# 12V_BOOST.net
KiCad netlist of a schematic drawn in Altium Designer
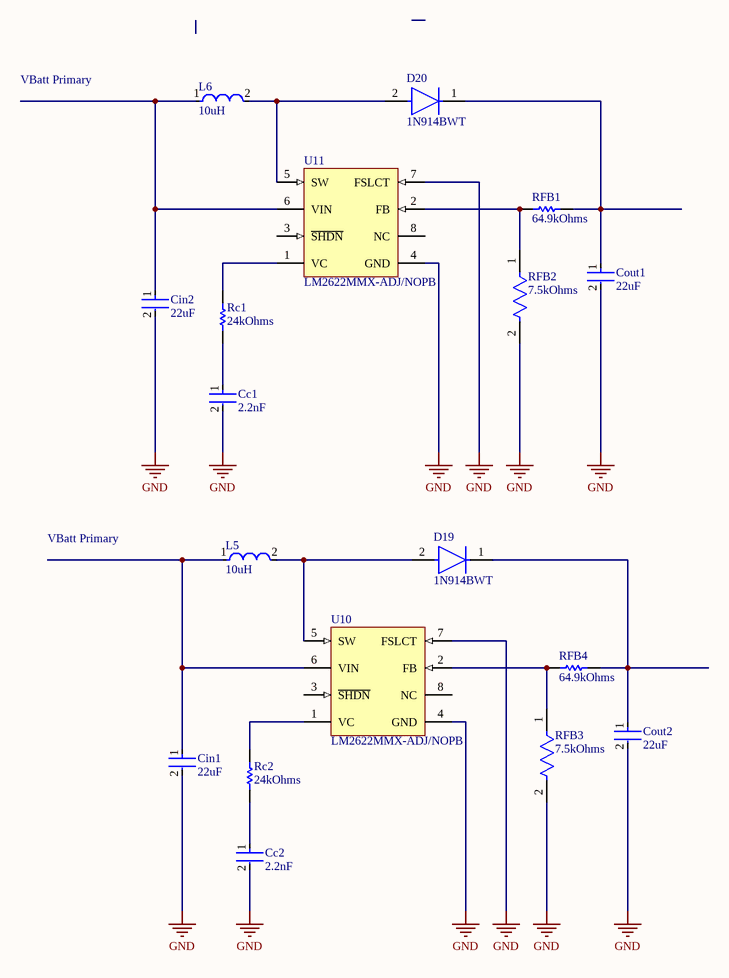
[diagram p0: 12V_BOOST.SchDoc]

(export (version "E")
  (design (tool "Eeschema 10.0.6"))
  (components
    (comp (ref "Cc1")
      (value "2.2nF")
      (footprint "FP-C0402-BB-MFG")
      (description "CAP CER 2200PF 25V 5% NP0 0402")
      (fields
        (field (name "OCTOPART") "https://octopart.com/c0402c222j3gactu-kemet-9145102")
        (field (name "MANUFACTURER") "Kemet")
      )
      (libsource (lib "Altium Content Vault") (part "b4654b650e69147ec39a6b967a45e02"))
    )
    (comp (ref "Cc2")
      (value "2.2nF")
      (footprint "FP-C0402-BB-MFG")
      (description "CAP CER 2200PF 25V 5% NP0 0402")
      (fields
        (field (name "OCTOPART") "https://octopart.com/c0402c222j3gactu-kemet-9145102")
        (field (name "MANUFACTURER") "Kemet")
      )
      (libsource (lib "Altium Content Vault") (part "b4654b650e69147ec39a6b967a45e02"))
    )
    (comp (ref "Cin1")
      (value "22uF")
      (footprint "FP-CL31-IPC_A")
      (description "Cap Ceramic 22uF 16V X5R ±20% SMD 1206 +85°C Embossed T/R")
      (fields (field (name "TOLERANCE") "20%") (field (name "VOLTAGE") "16V"))
      (libsource (lib "Altium Content Vault") (part "b4654b650e69147ec39a6b967a45e02"))
    )
    (comp (ref "Cin2")
      (value "22uF")
      (footprint "FP-CL31-IPC_A")
      (description "Cap Ceramic 22uF 16V X5R ±20% SMD 1206 +85°C Embossed T/R")
      (fields (field (name "TOLERANCE") "20%") (field (name "VOLTAGE") "16V"))
      (libsource (lib "Altium Content Vault") (part "b4654b650e69147ec39a6b967a45e02"))
    )
    (comp (ref "Cout1")
      (value "22uF")
      (footprint "FP-CL31-IPC_A")
      (description "Cap Ceramic 22uF 16V X5R ±20% SMD 1206 +85°C Embossed T/R")
      (fields (field (name "TOLERANCE") "20%") (field (name "VOLTAGE") "16V"))
      (libsource (lib "Altium Content Vault") (part "b4654b650e69147ec39a6b967a45e02"))
    )
    (comp (ref "Cout2")
      (value "22uF")
      (footprint "FP-CL31-IPC_A")
      (description "Cap Ceramic 22uF 16V X5R ±20% SMD 1206 +85°C Embossed T/R")
      (fields (field (name "TOLERANCE") "20%") (field (name "VOLTAGE") "16V"))
      (libsource (lib "Altium Content Vault") (part "b4654b650e69147ec39a6b967a45e02"))
    )
    (comp (ref "D19")
      (value "1N914BWT")
      (footprint "FP-502-01-MFG")
      (description "DIODE GEN PURP 75V 200MA SOD523F")
      (fields
        (field (name "OCTOPART") "https://octopart.com/1n914bwt-on+semiconductor-84323166")
        (field (name "MANUFACTURER") "ON Semiconductor")
      )
      (libsource (lib "Altium Content Vault") (part "d7152d700b627762746794eb795d46e"))
    )
    (comp (ref "D20")
      (value "1N914BWT")
      (footprint "FP-502-01-MFG")
      (description "DIODE GEN PURP 75V 200MA SOD523F")
      (fields
        (field (name "OCTOPART") "https://octopart.com/1n914bwt-on+semiconductor-84323166")
        (field (name "MANUFACTURER") "ON Semiconductor")
      )
      (libsource (lib "Altium Content Vault") (part "d7152d700b627762746794eb795d46e"))
    )
    (comp (ref "L5")
      (value "10uH")
      (footprint "FP-MLZ1608-IPC_C")
      (description "Shielded Multilayer Inductor 10uH ±20% 250mA 1365mΩ SMD 0603")
      (fields (field (name "TOLERANCE") "20%"))
      (libsource (lib "Altium Content Vault") (part "725321dda6339637d4d059423bc1c3c"))
    )
    (comp (ref "L6")
      (value "10uH")
      (footprint "FP-MLZ1608-IPC_C")
      (description "Shielded Multilayer Inductor 10uH ±20% 250mA 1365mΩ SMD 0603")
      (fields (field (name "TOLERANCE") "20%"))
      (libsource (lib "Altium Content Vault") (part "725321dda6339637d4d059423bc1c3c"))
    )
    (comp (ref "Rc1")
      (value "24kOhms")
      (footprint "RESC1005X40X25ML05T05")
      (fields (field (name "PART NUMBER") "CRCW040224K0FKED") (field (name "MANUFACTURER") "Vishay Dale"))
      (libsource (lib "Altium Content Vault") (part "RES"))
    )
    (comp (ref "Rc2")
      (value "24kOhms")
      (footprint "RESC1005X40X25ML05T05")
      (fields (field (name "PART NUMBER") "CRCW040224K0FKED") (field (name "MANUFACTURER") "Vishay Dale"))
      (libsource (lib "Altium Content Vault") (part "RES"))
    )
    (comp (ref "RFB1")
      (value "64.9kOhms")
      (footprint "RESC3216X70X50NL05T20")
      (fields (field (name "PART NUMBER") "ERJ-8ENF64R9V") (field (name "MANUFACTURER") "Panasonic"))
      (libsource (lib "Altium Content Vault") (part "RES"))
    )
    (comp (ref "RFB2")
      (value "7.5kOhms")
      (footprint "FP-ERJ3EK-MFG")
      (description "RES SMD 7.5K OHM 1% 1/10W 0603")
      (fields (field (name "TOLERANCE") "1%"))
      (libsource (lib "Altium Content Vault") (part "1029c3af85768c4190bb7ad29bc67b5"))
    )
    (comp (ref "RFB3")
      (value "7.5kOhms")
      (footprint "FP-ERJ3EK-MFG")
      (description "RES SMD 7.5K OHM 1% 1/10W 0603")
      (fields (field (name "TOLERANCE") "1%"))
      (libsource (lib "Altium Content Vault") (part "1029c3af85768c4190bb7ad29bc67b5"))
    )
    (comp (ref "RFB4")
      (value "64.9kOhms")
      (footprint "RESC3216X70X50NL05T20")
      (fields (field (name "PART NUMBER") "ERJ-8ENF64R9V") (field (name "MANUFACTURER") "Panasonic"))
      (libsource (lib "Altium Content Vault") (part "RES"))
    )
    (comp (ref "U10")
      (value "LM2622MMX-ADJ/NOPB")
      (footprint "DGK0008A_M")
      (description "600kHz/1.3MHz Step-up PWM DC/DC Converter, 8-pin MSOP, Pb-Free")
      (fields (field (name "MANUFACTURER") "Texas Instruments"))
      (libsource (lib "Altium Content Vault") (part "PM-CNTL-LM2622MM-8"))
    )
    (comp (ref "U11")
      (value "LM2622MMX-ADJ/NOPB")
      (footprint "DGK0008A_M")
      (description "600kHz/1.3MHz Step-up PWM DC/DC Converter, 8-pin MSOP, Pb-Free")
      (fields (field (name "MANUFACTURER") "Texas Instruments"))
      (libsource (lib "Altium Content Vault") (part "PM-CNTL-LM2622MM-8"))
    )
  )
  (nets
    (net (code "1") (name "GND") (class "Default")
      (node (ref "Cc1") (pin "2") (pinfunction "2_2") (pintype "passive"))
      (node (ref "Cc2") (pin "2") (pinfunction "2_2") (pintype "passive"))
      (node (ref "Cin1") (pin "2") (pinfunction "2_2") (pintype "passive"))
      (node (ref "Cin2") (pin "2") (pinfunction "2_2") (pintype "passive"))
      (node (ref "Cout1") (pin "2") (pinfunction "2_2") (pintype "passive"))
      (node (ref "Cout2") (pin "2") (pinfunction "2_2") (pintype "passive"))
      (node (ref "RFB2") (pin "2") (pinfunction "2_2") (pintype "passive"))
      (node (ref "RFB3") (pin "2") (pinfunction "2_2") (pintype "passive"))
      (node (ref "U10") (pin "4") (pinfunction "GND_4") (pintype "power_in"))
      (node (ref "U10") (pin "7") (pinfunction "FSLCT_7") (pintype "input"))
      (node (ref "U11") (pin "4") (pinfunction "GND_4") (pintype "power_in"))
      (node (ref "U11") (pin "7") (pinfunction "FSLCT_7") (pintype "input"))
    )
    (net (code "2") (name "Net-(Cc1-Pad1)") (class "Default")
      (node (ref "Cc1") (pin "1") (pinfunction "1_1") (pintype "passive"))
      (node (ref "Rc1") (pin "2") (pinfunction "2_2") (pintype "passive"))
    )
    (net (code "3") (name "Net-(Cc2-Pad1)") (class "Default")
      (node (ref "Cc2") (pin "1") (pinfunction "1_1") (pintype "passive"))
      (node (ref "Rc2") (pin "2") (pinfunction "2_2") (pintype "passive"))
    )
    (net (code "4") (name "Net-(D19-A)") (class "Default")
      (node (ref "D19") (pin "2") (pinfunction "A_2") (pintype "passive"))
      (node (ref "L5") (pin "2") (pinfunction "2_2") (pintype "passive"))
      (node (ref "U10") (pin "5") (pinfunction "SW_5") (pintype "input"))
    )
    (net (code "5") (name "Net-(D19-C)") (class "Default")
      (node (ref "Cout2") (pin "1") (pinfunction "1_1") (pintype "passive"))
      (node (ref "D19") (pin "1") (pinfunction "C_1") (pintype "passive"))
      (node (ref "RFB4") (pin "2") (pinfunction "2_2") (pintype "passive"))
    )
    (net (code "6") (name "Net-(D20-A)") (class "Default")
      (node (ref "D20") (pin "2") (pinfunction "A_2") (pintype "passive"))
      (node (ref "L6") (pin "2") (pinfunction "2_2") (pintype "passive"))
      (node (ref "U11") (pin "5") (pinfunction "SW_5") (pintype "input"))
    )
    (net (code "7") (name "Net-(D20-C)") (class "Default")
      (node (ref "Cout1") (pin "1") (pinfunction "1_1") (pintype "passive"))
      (node (ref "D20") (pin "1") (pinfunction "C_1") (pintype "passive"))
      (node (ref "RFB1") (pin "2") (pinfunction "2_2") (pintype "passive"))
    )
    (net (code "8") (name "Net-(U10-FB)") (class "Default")
      (node (ref "RFB3") (pin "1") (pinfunction "1_1") (pintype "passive"))
      (node (ref "RFB4") (pin "1") (pinfunction "1_1") (pintype "passive"))
      (node (ref "U10") (pin "2") (pinfunction "FB_2") (pintype "input"))
    )
    (net (code "9") (name "Net-(U10-VC)") (class "Default")
      (node (ref "Rc2") (pin "1") (pinfunction "1_1") (pintype "passive"))
      (node (ref "U10") (pin "1") (pinfunction "VC_1") (pintype "power_in"))
    )
    (net (code "10") (name "Net-(U10-VIN)") (class "Default")
      (node (ref "Cin1") (pin "1") (pinfunction "1_1") (pintype "passive"))
      (node (ref "L5") (pin "1") (pinfunction "1_1") (pintype "passive"))
      (node (ref "U10") (pin "6") (pinfunction "VIN_6") (pintype "power_in"))
    )
    (net (code "11") (name "Net-(U11-FB)") (class "Default")
      (node (ref "RFB1") (pin "1") (pinfunction "1_1") (pintype "passive"))
      (node (ref "RFB2") (pin "1") (pinfunction "1_1") (pintype "passive"))
      (node (ref "U11") (pin "2") (pinfunction "FB_2") (pintype "input"))
    )
    (net (code "12") (name "Net-(U11-VC)") (class "Default")
      (node (ref "Rc1") (pin "1") (pinfunction "1_1") (pintype "passive"))
      (node (ref "U11") (pin "1") (pinfunction "VC_1") (pintype "power_in"))
    )
    (net (code "13") (name "Net-(U11-VIN)") (class "Default")
      (node (ref "Cin2") (pin "1") (pinfunction "1_1") (pintype "passive"))
      (node (ref "L6") (pin "1") (pinfunction "1_1") (pintype "passive"))
      (node (ref "U11") (pin "6") (pinfunction "VIN_6") (pintype "power_in"))
    )
    (net (code "14") (name "unconnected-(U10-NC-Pad8)") (class "Default")
      (node (ref "U10") (pin "8") (pinfunction "NC_8") (pintype "passive"))
    )
    (net (code "15") (name "unconnected-(U10-~{SHDN}-Pad3)") (class "Default")
      (node (ref "U10") (pin "3") (pinfunction "~{SHDN}_3") (pintype "input"))
    )
    (net (code "16") (name "unconnected-(U11-NC-Pad8)") (class "Default")
      (node (ref "U11") (pin "8") (pinfunction "NC_8") (pintype "passive"))
    )
    (net (code "17") (name "unconnected-(U11-~{SHDN}-Pad3)") (class "Default")
      (node (ref "U11") (pin "3") (pinfunction "~{SHDN}_3") (pintype "input"))
    )
  )
)
